# clogic.net
KiCad netlist of a schematic drawn in EAGLE
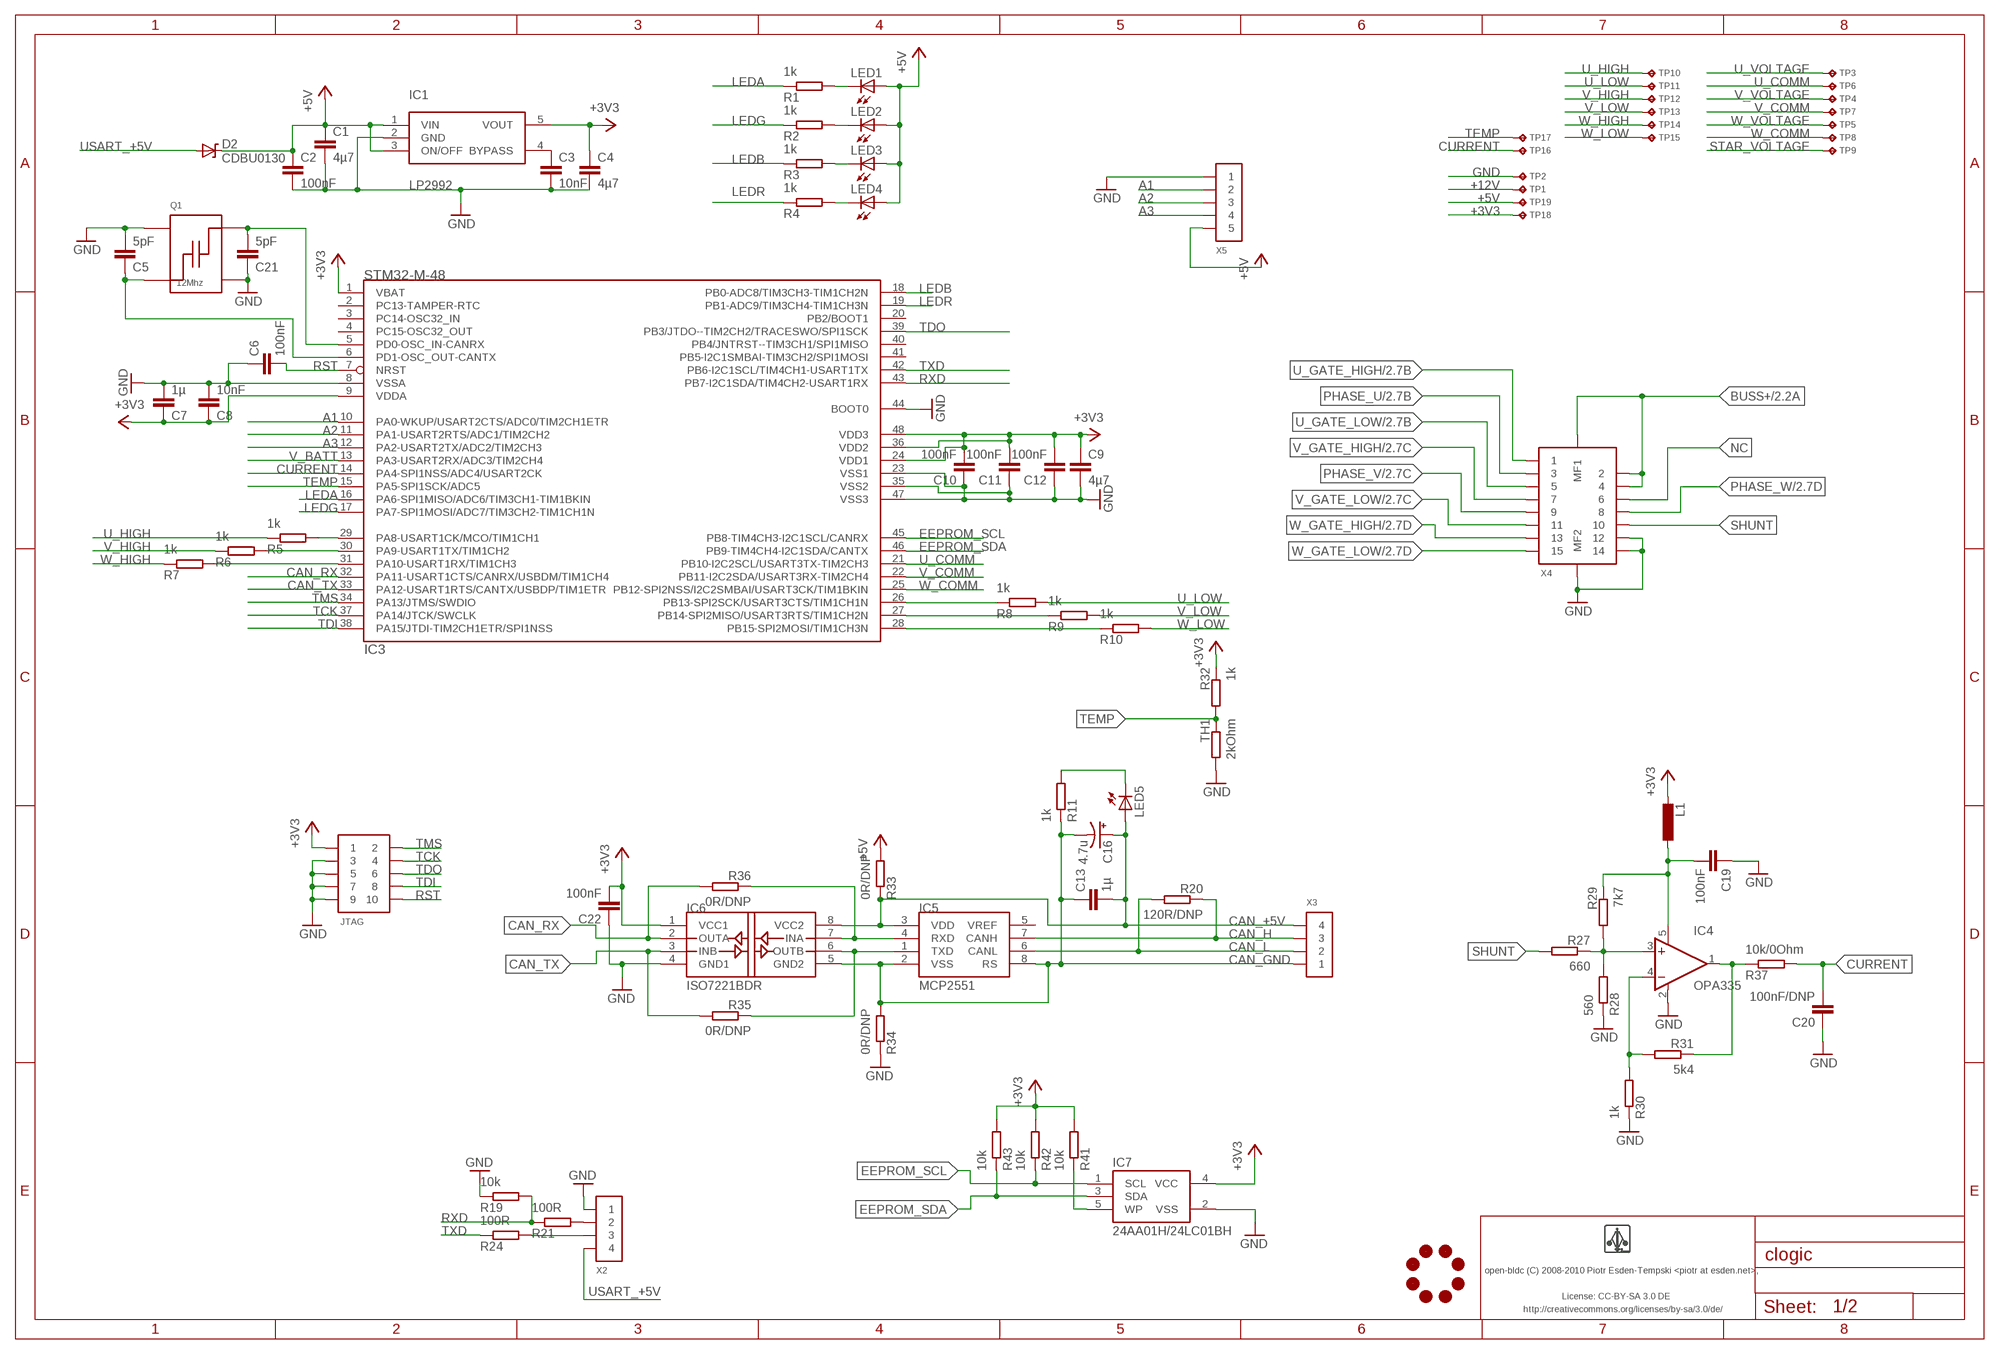
[diagram p0: schematic, sheet 1]
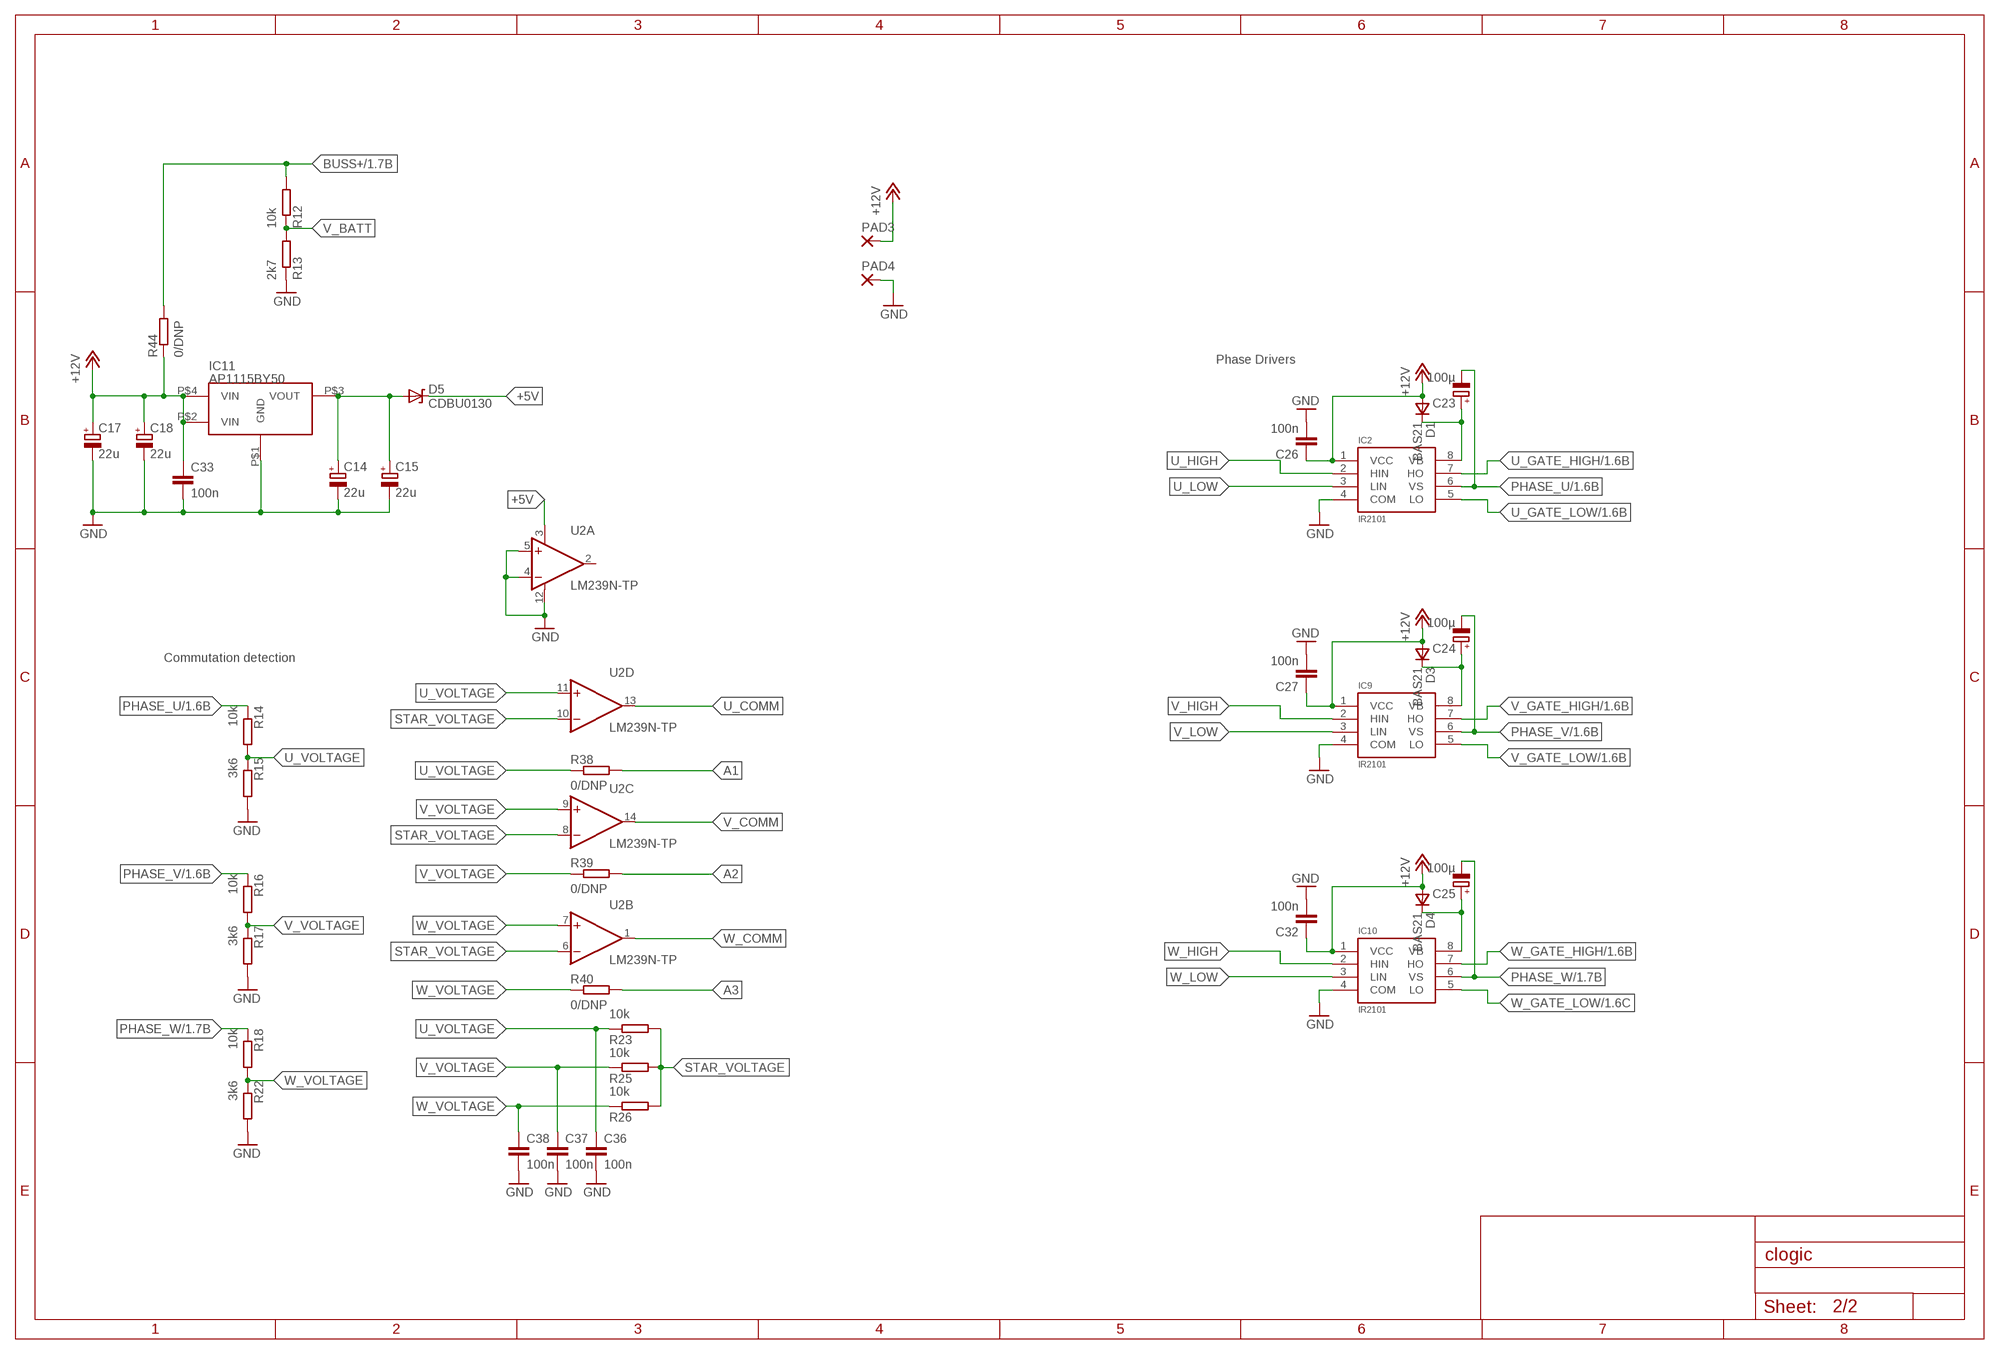
[diagram p1: schematic, sheet 2]

(export (version "E")
  (design (tool "Eeschema 10.0.6"))
  (components
    (comp (ref "C1")
      (value "4µ7")
      (footprint "eagle-import:0603-CAP")
      (libsource (lib "eagle-import") (part "CAPACITOR-0603"))
    )
    (comp (ref "C2")
      (value "100nF")
      (footprint "eagle-import:0603-CAP")
      (libsource (lib "eagle-import") (part "CAPACITOR-0603"))
    )
    (comp (ref "C3")
      (value "10nF")
      (footprint "eagle-import:0603-CAP")
      (libsource (lib "eagle-import") (part "CAPACITOR-0603"))
    )
    (comp (ref "C4")
      (value "4µ7")
      (footprint "eagle-import:0603-CAP")
      (libsource (lib "eagle-import") (part "CAPACITOR-0603"))
    )
    (comp (ref "C5")
      (value "5pF")
      (footprint "eagle-import:0603-CAP")
      (libsource (lib "eagle-import") (part "CAPACITOR-0603"))
    )
    (comp (ref "C6")
      (value "100nF")
      (footprint "eagle-import:0603-CAP")
      (libsource (lib "eagle-import") (part "CAPACITOR-0603"))
    )
    (comp (ref "C7")
      (value "1µ")
      (footprint "eagle-import:0603-CAP")
      (libsource (lib "eagle-import") (part "CAPACITOR-0603"))
    )
    (comp (ref "C8")
      (value "10nF")
      (footprint "eagle-import:0603-CAP")
      (libsource (lib "eagle-import") (part "CAPACITOR-0603"))
    )
    (comp (ref "C9")
      (value "4µ7")
      (footprint "eagle-import:0603-CAP")
      (libsource (lib "eagle-import") (part "CAPACITOR-0603"))
    )
    (comp (ref "C10")
      (value "100nF")
      (footprint "eagle-import:0603-CAP")
      (libsource (lib "eagle-import") (part "CAPACITOR-0603"))
    )
    (comp (ref "C11")
      (value "100nF")
      (footprint "eagle-import:0603-CAP")
      (libsource (lib "eagle-import") (part "CAPACITOR-0603"))
    )
    (comp (ref "C12")
      (value "100nF")
      (footprint "eagle-import:0603-CAP")
      (libsource (lib "eagle-import") (part "CAPACITOR-0603"))
    )
    (comp (ref "C13")
      (value "1µ")
      (footprint "eagle-import:0603-CAP")
      (libsource (lib "eagle-import") (part "CAPACITOR-0603"))
    )
    (comp (ref "C16")
      (value "4.7u")
      (footprint "eagle-import:CAP_0805TANT_F95")
      (libsource (lib "eagle-import") (part "CPOL-US"))
    )
    (comp (ref "C19")
      (value "100nF")
      (footprint "eagle-import:0603-CAP")
      (libsource (lib "eagle-import") (part "CAPACITOR-0603"))
    )
    (comp (ref "C20")
      (value "100nF/DNP")
      (footprint "eagle-import:0603-CAP")
      (libsource (lib "eagle-import") (part "CAPACITOR-0603"))
    )
    (comp (ref "C21")
      (value "5pF")
      (footprint "eagle-import:0603-CAP")
      (libsource (lib "eagle-import") (part "CAPACITOR-0603"))
    )
    (comp (ref "C22")
      (value "100nF")
      (footprint "eagle-import:0603-CAP")
      (libsource (lib "eagle-import") (part "CAPACITOR-0603"))
    )
    (comp (ref "D2")
      (value "CDBU0130")
      (footprint "eagle-import:0603-LED")
      (libsource (lib "eagle-import") (part "DIODE-ZENER-0603"))
    )
    (comp (ref "IC1")
      (value "LP2992")
      (footprint "eagle-import:SOT23-5")
      (libsource (lib "eagle-import") (part "LP2992"))
    )
    (comp (ref "IC3")
      (value "STM32-M-48")
      (footprint "eagle-import:LQFP48")
      (libsource (lib "eagle-import") (part "STM32-M-48"))
    )
    (comp (ref "IC4")
      (value "OPA335")
      (footprint "eagle-import:SOT23-5")
      (libsource (lib "eagle-import") (part "OPA335"))
    )
    (comp (ref "IC5")
      (value "MCP2551")
      (footprint "eagle-import:SO8")
      (libsource (lib "eagle-import") (part "MCP2551"))
    )
    (comp (ref "IC6")
      (value "ISO7221BDR")
      (footprint "eagle-import:SO8")
      (libsource (lib "eagle-import") (part "ISO7221"))
    )
    (comp (ref "IC7")
      (value "24AA01H/24LC01BH")
      (footprint "eagle-import:SOT23-5")
      (libsource (lib "eagle-import") (part "EEPROM-I2C"))
    )
    (comp (ref "JL1")
      (value "JOBY_LOGO-6MIL")
      (footprint "eagle-import:JOBY_LOGO_6MIL")
      (libsource (lib "eagle-import") (part "JOBY_LOGO-6MIL"))
    )
    (comp (ref "JTAG")
      (value "CONN_5-2-FTSH-V")
      (footprint "eagle-import:FTSH-105-DV")
      (libsource (lib "eagle-import") (part "CONN_5-2-FTSH-V"))
    )
    (comp (ref "L1")
      (value "INDUCTOR-0603")
      (footprint "eagle-import:0603-IND")
      (libsource (lib "eagle-import") (part "INDUCTOR-0603"))
    )
    (comp (ref "LED1")
      (value "AMBER")
      (footprint "eagle-import:0603-LED")
      (libsource (lib "eagle-import") (part "LED-0603"))
    )
    (comp (ref "LED2")
      (value "GREEN")
      (footprint "eagle-import:0603-LED")
      (libsource (lib "eagle-import") (part "LED-0603"))
    )
    (comp (ref "LED3")
      (value "BLUE")
      (footprint "eagle-import:0603-LED")
      (libsource (lib "eagle-import") (part "LED-0603"))
    )
    (comp (ref "LED4")
      (value "RED")
      (footprint "eagle-import:0603-LED")
      (libsource (lib "eagle-import") (part "LED-0603"))
    )
    (comp (ref "LED5")
      (value "WHITE")
      (footprint "eagle-import:0603-LED")
      (libsource (lib "eagle-import") (part "LED-0603"))
    )
    (comp (ref "Q1")
      (value "12Mhz")
      (footprint "eagle-import:ABM8")
      (libsource (lib "eagle-import") (part "ABM8"))
    )
    (comp (ref "R1")
      (value "1k")
      (footprint "eagle-import:0603-RES")
      (libsource (lib "eagle-import") (part "RESISTOR-0603"))
    )
    (comp (ref "R2")
      (value "1k")
      (footprint "eagle-import:0603-RES")
      (libsource (lib "eagle-import") (part "RESISTOR-0603"))
    )
    (comp (ref "R3")
      (value "1k")
      (footprint "eagle-import:0603-RES")
      (libsource (lib "eagle-import") (part "RESISTOR-0603"))
    )
    (comp (ref "R4")
      (value "1k")
      (footprint "eagle-import:0603-RES")
      (libsource (lib "eagle-import") (part "RESISTOR-0603"))
    )
    (comp (ref "R5")
      (value "1k")
      (footprint "eagle-import:0603-RES")
      (libsource (lib "eagle-import") (part "RESISTOR-0603"))
    )
    (comp (ref "R6")
      (value "1k")
      (footprint "eagle-import:0603-RES")
      (libsource (lib "eagle-import") (part "RESISTOR-0603"))
    )
    (comp (ref "R7")
      (value "1k")
      (footprint "eagle-import:0603-RES")
      (libsource (lib "eagle-import") (part "RESISTOR-0603"))
    )
    (comp (ref "R8")
      (value "1k")
      (footprint "eagle-import:0603-RES")
      (libsource (lib "eagle-import") (part "RESISTOR-0603"))
    )
    (comp (ref "R9")
      (value "1k")
      (footprint "eagle-import:0603-RES")
      (libsource (lib "eagle-import") (part "RESISTOR-0603"))
    )
    (comp (ref "R10")
      (value "1k")
      (footprint "eagle-import:0603-RES")
      (libsource (lib "eagle-import") (part "RESISTOR-0603"))
    )
    (comp (ref "R11")
      (value "1k")
      (footprint "eagle-import:0603-RES")
      (libsource (lib "eagle-import") (part "RESISTOR-0603"))
    )
    (comp (ref "R19")
      (value "10k")
      (footprint "eagle-import:0603-RES")
      (libsource (lib "eagle-import") (part "RESISTOR-0603"))
    )
    (comp (ref "R20")
      (value "120R/DNP")
      (footprint "eagle-import:0603-RES")
      (libsource (lib "eagle-import") (part "RESISTOR-0603"))
    )
    (comp (ref "R21")
      (value "100R")
      (footprint "eagle-import:0603-RES")
      (libsource (lib "eagle-import") (part "RESISTOR-0603"))
    )
    (comp (ref "R24")
      (value "100R")
      (footprint "eagle-import:0603-RES")
      (libsource (lib "eagle-import") (part "RESISTOR-0603"))
    )
    (comp (ref "R27")
      (value "660")
      (footprint "eagle-import:0603-RES")
      (libsource (lib "eagle-import") (part "RESISTOR-0603"))
    )
    (comp (ref "R28")
      (value "560")
      (footprint "eagle-import:0603-RES")
      (libsource (lib "eagle-import") (part "RESISTOR-0603"))
    )
    (comp (ref "R29")
      (value "7k7")
      (footprint "eagle-import:0603-RES")
      (libsource (lib "eagle-import") (part "RESISTOR-0603"))
    )
    (comp (ref "R30")
      (value "1k")
      (footprint "eagle-import:0603-RES")
      (libsource (lib "eagle-import") (part "RESISTOR-0603"))
    )
    (comp (ref "R31")
      (value "5k4")
      (footprint "eagle-import:0603-RES")
      (libsource (lib "eagle-import") (part "RESISTOR-0603"))
    )
    (comp (ref "R32")
      (value "1k")
      (footprint "eagle-import:0603-RES")
      (libsource (lib "eagle-import") (part "RESISTOR-0603"))
    )
    (comp (ref "R33")
      (value "0R/DNP")
      (footprint "eagle-import:0603-RES")
      (libsource (lib "eagle-import") (part "RESISTOR-0603"))
    )
    (comp (ref "R34")
      (value "0R/DNP")
      (footprint "eagle-import:0603-RES")
      (libsource (lib "eagle-import") (part "RESISTOR-0603"))
    )
    (comp (ref "R35")
      (value "0R/DNP")
      (footprint "eagle-import:0603-RES")
      (libsource (lib "eagle-import") (part "RESISTOR-0603"))
    )
    (comp (ref "R36")
      (value "0R/DNP")
      (footprint "eagle-import:0603-RES")
      (libsource (lib "eagle-import") (part "RESISTOR-0603"))
    )
    (comp (ref "R37")
      (value "10k/0Ohm")
      (footprint "eagle-import:0603-RES")
      (libsource (lib "eagle-import") (part "RESISTOR-0603"))
    )
    (comp (ref "R41")
      (value "10k")
      (footprint "eagle-import:0603-RES")
      (libsource (lib "eagle-import") (part "RESISTOR-0603"))
    )
    (comp (ref "R42")
      (value "10k")
      (footprint "eagle-import:0603-RES")
      (libsource (lib "eagle-import") (part "RESISTOR-0603"))
    )
    (comp (ref "R43")
      (value "10k")
      (footprint "eagle-import:0603-RES")
      (libsource (lib "eagle-import") (part "RESISTOR-0603"))
    )
    (comp (ref "TH1")
      (value "2kOhm")
      (footprint "eagle-import:0603-RES")
      (libsource (lib "eagle-import") (part "RESISTOR-0603"))
    )
    (comp (ref "TP1")
      (value "TP-09RSMD")
      (footprint "eagle-import:TP09R")
      (libsource (lib "eagle-import") (part "TP-09RSMD"))
    )
    (comp (ref "TP2")
      (value "TP-09RSMD")
      (footprint "eagle-import:TP09R")
      (libsource (lib "eagle-import") (part "TP-09RSMD"))
    )
    (comp (ref "TP3")
      (value "TP-09RSMD")
      (footprint "eagle-import:TP09R")
      (libsource (lib "eagle-import") (part "TP-09RSMD"))
    )
    (comp (ref "TP4")
      (value "TP-09RSMD")
      (footprint "eagle-import:TP09R")
      (libsource (lib "eagle-import") (part "TP-09RSMD"))
    )
    (comp (ref "TP5")
      (value "TP-09RSMD")
      (footprint "eagle-import:TP09R")
      (libsource (lib "eagle-import") (part "TP-09RSMD"))
    )
    (comp (ref "TP6")
      (value "TP-09RSMD")
      (footprint "eagle-import:TP09R")
      (libsource (lib "eagle-import") (part "TP-09RSMD"))
    )
    (comp (ref "TP7")
      (value "TP-09RSMD")
      (footprint "eagle-import:TP09R")
      (libsource (lib "eagle-import") (part "TP-09RSMD"))
    )
    (comp (ref "TP8")
      (value "TP-09RSMD")
      (footprint "eagle-import:TP09R")
      (libsource (lib "eagle-import") (part "TP-09RSMD"))
    )
    (comp (ref "TP9")
      (value "TP-09RSMD")
      (footprint "eagle-import:TP09R")
      (libsource (lib "eagle-import") (part "TP-09RSMD"))
    )
    (comp (ref "TP10")
      (value "TP-09RSMD")
      (footprint "eagle-import:TP09R")
      (libsource (lib "eagle-import") (part "TP-09RSMD"))
    )
    (comp (ref "TP11")
      (value "TP-09RSMD")
      (footprint "eagle-import:TP09R")
      (libsource (lib "eagle-import") (part "TP-09RSMD"))
    )
    (comp (ref "TP12")
      (value "TP-09RSMD")
      (footprint "eagle-import:TP09R")
      (libsource (lib "eagle-import") (part "TP-09RSMD"))
    )
    (comp (ref "TP13")
      (value "TP-09RSMD")
      (footprint "eagle-import:TP09R")
      (libsource (lib "eagle-import") (part "TP-09RSMD"))
    )
    (comp (ref "TP14")
      (value "TP-09RSMD")
      (footprint "eagle-import:TP09R")
      (libsource (lib "eagle-import") (part "TP-09RSMD"))
    )
    (comp (ref "TP15")
      (value "TP-09RSMD")
      (footprint "eagle-import:TP09R")
      (libsource (lib "eagle-import") (part "TP-09RSMD"))
    )
    (comp (ref "TP16")
      (value "TP-09RSMD")
      (footprint "eagle-import:TP09R")
      (libsource (lib "eagle-import") (part "TP-09RSMD"))
    )
    (comp (ref "TP17")
      (value "TP-09RSMD")
      (footprint "eagle-import:TP09R")
      (libsource (lib "eagle-import") (part "TP-09RSMD"))
    )
    (comp (ref "TP18")
      (value "TP-09RSMD")
      (footprint "eagle-import:TP09R")
      (libsource (lib "eagle-import") (part "TP-09RSMD"))
    )
    (comp (ref "TP19")
      (value "TP-09RSMD")
      (footprint "eagle-import:TP09R")
      (libsource (lib "eagle-import") (part "TP-09RSMD"))
    )
    (comp (ref "U$1")
      (value "LOGO")
      (footprint "eagle-import:LOGO")
      (libsource (lib "eagle-import") (part "LOGO-NORM"))
    )
    (comp (ref "X2")
      (value "CONN_4-1-53261")
      (footprint "eagle-import:PB-53261-04")
      (libsource (lib "eagle-import") (part "CONN_4-1-53261"))
    )
    (comp (ref "X3")
      (value "CONN_4-1-53261")
      (footprint "eagle-import:PB-53261-04")
      (libsource (lib "eagle-import") (part "CONN_4-1-53261"))
    )
    (comp (ref "X4")
      (value "CONN_15-2-2MT-DF9")
      (footprint "eagle-import:DF9-15")
      (libsource (lib "eagle-import") (part "CONN_15-2-2MT-DF9"))
    )
    (comp (ref "X5")
      (value "CONN_5-1-53261")
      (footprint "eagle-import:PB-53261-05")
      (libsource (lib "eagle-import") (part "CONN_5-1-53261"))
    )
    (comp (ref "C14")
      (value "22u")
      (footprint "eagle-import:0805-POL-CAP")
      (libsource (lib "eagle-import") (part "CAPACITOR-POL-0805"))
    )
    (comp (ref "C15")
      (value "22u")
      (footprint "eagle-import:0805-POL-CAP")
      (libsource (lib "eagle-import") (part "CAPACITOR-POL-0805"))
    )
    (comp (ref "C17")
      (value "22u")
      (footprint "eagle-import:0805-POL-CAP")
      (libsource (lib "eagle-import") (part "CAPACITOR-POL-0805"))
    )
    (comp (ref "C18")
      (value "22u")
      (footprint "eagle-import:0805-POL-CAP")
      (libsource (lib "eagle-import") (part "CAPACITOR-POL-0805"))
    )
    (comp (ref "C23")
      (value "100µ")
      (footprint "eagle-import:0805-POL-CAP")
      (libsource (lib "eagle-import") (part "CAPACITOR-POL-0805"))
    )
    (comp (ref "C24")
      (value "100µ")
      (footprint "eagle-import:0805-POL-CAP")
      (libsource (lib "eagle-import") (part "CAPACITOR-POL-0805"))
    )
    (comp (ref "C25")
      (value "100µ")
      (footprint "eagle-import:0805-POL-CAP")
      (libsource (lib "eagle-import") (part "CAPACITOR-POL-0805"))
    )
    (comp (ref "C26")
      (value "100n")
      (footprint "eagle-import:0603-CAP")
      (libsource (lib "eagle-import") (part "CAPACITOR-0603"))
    )
    (comp (ref "C27")
      (value "100n")
      (footprint "eagle-import:0603-CAP")
      (libsource (lib "eagle-import") (part "CAPACITOR-0603"))
    )
    (comp (ref "C32")
      (value "100n")
      (footprint "eagle-import:0603-CAP")
      (libsource (lib "eagle-import") (part "CAPACITOR-0603"))
    )
    (comp (ref "C33")
      (value "100n")
      (footprint "eagle-import:0603-CAP")
      (libsource (lib "eagle-import") (part "CAPACITOR-0603"))
    )
    (comp (ref "C36")
      (value "100n")
      (footprint "eagle-import:0603-CAP")
      (libsource (lib "eagle-import") (part "CAPACITOR-0603"))
    )
    (comp (ref "C37")
      (value "100n")
      (footprint "eagle-import:0603-CAP")
      (libsource (lib "eagle-import") (part "CAPACITOR-0603"))
    )
    (comp (ref "C38")
      (value "100n")
      (footprint "eagle-import:0603-CAP")
      (libsource (lib "eagle-import") (part "CAPACITOR-0603"))
    )
    (comp (ref "D1")
      (value "BAS21")
      (footprint "eagle-import:SOT-23")
      (libsource (lib "eagle-import") (part "VAR2SOT23"))
    )
    (comp (ref "D3")
      (value "BAS21")
      (footprint "eagle-import:SOT-23")
      (libsource (lib "eagle-import") (part "VAR2SOT23"))
    )
    (comp (ref "D4")
      (value "BAS21")
      (footprint "eagle-import:SOT-23")
      (libsource (lib "eagle-import") (part "VAR2SOT23"))
    )
    (comp (ref "D5")
      (value "CDBU0130")
      (footprint "eagle-import:0603-LED")
      (libsource (lib "eagle-import") (part "DIODE-ZENER-0603"))
    )
    (comp (ref "IC2")
      (value "IR2101")
      (footprint "eagle-import:SO-8")
      (libsource (lib "eagle-import") (part "IR2101"))
    )
    (comp (ref "IC9")
      (value "IR2101")
      (footprint "eagle-import:SO-8")
      (libsource (lib "eagle-import") (part "IR2101"))
    )
    (comp (ref "IC10")
      (value "IR2101")
      (footprint "eagle-import:SO-8")
      (libsource (lib "eagle-import") (part "IR2101"))
    )
    (comp (ref "IC11")
      (value "AP1115BY50")
      (footprint "eagle-import:SOT89")
      (libsource (lib "eagle-import") (part "AP1115BY50"))
    )
    (comp (ref "PAD3")
      (value "SMD5")
      (footprint "eagle-import:SMD2,54-5,08")
      (libsource (lib "eagle-import") (part "SMD5"))
    )
    (comp (ref "PAD4")
      (value "SMD5")
      (footprint "eagle-import:SMD2,54-5,08")
      (libsource (lib "eagle-import") (part "SMD5"))
    )
    (comp (ref "R12")
      (value "10k")
      (footprint "eagle-import:0603-RES")
      (libsource (lib "eagle-import") (part "RESISTOR-0603"))
    )
    (comp (ref "R13")
      (value "2k7")
      (footprint "eagle-import:0603-RES")
      (libsource (lib "eagle-import") (part "RESISTOR-0603"))
    )
    (comp (ref "R14")
      (value "10k")
      (footprint "eagle-import:0603-RES")
      (libsource (lib "eagle-import") (part "RESISTOR-0603"))
    )
    (comp (ref "R15")
      (value "3k6")
      (footprint "eagle-import:0603-RES")
      (libsource (lib "eagle-import") (part "RESISTOR-0603"))
    )
    (comp (ref "R16")
      (value "10k")
      (footprint "eagle-import:0603-RES")
      (libsource (lib "eagle-import") (part "RESISTOR-0603"))
    )
    (comp (ref "R17")
      (value "3k6")
      (footprint "eagle-import:0603-RES")
      (libsource (lib "eagle-import") (part "RESISTOR-0603"))
    )
    (comp (ref "R18")
      (value "10k")
      (footprint "eagle-import:0603-RES")
      (libsource (lib "eagle-import") (part "RESISTOR-0603"))
    )
    (comp (ref "R22")
      (value "3k6")
      (footprint "eagle-import:0603-RES")
      (libsource (lib "eagle-import") (part "RESISTOR-0603"))
    )
    (comp (ref "R23")
      (value "10k")
      (footprint "eagle-import:0603-RES")
      (libsource (lib "eagle-import") (part "RESISTOR-0603"))
    )
    (comp (ref "R25")
      (value "10k")
      (footprint "eagle-import:0603-RES")
      (libsource (lib "eagle-import") (part "RESISTOR-0603"))
    )
    (comp (ref "R26")
      (value "10k")
      (footprint "eagle-import:0603-RES")
      (libsource (lib "eagle-import") (part "RESISTOR-0603"))
    )
    (comp (ref "R38")
      (value "0/DNP")
      (footprint "eagle-import:0603-RES")
      (libsource (lib "eagle-import") (part "RESISTOR-0603"))
    )
    (comp (ref "R39")
      (value "0/DNP")
      (footprint "eagle-import:0603-RES")
      (libsource (lib "eagle-import") (part "RESISTOR-0603"))
    )
    (comp (ref "R40")
      (value "0/DNP")
      (footprint "eagle-import:0603-RES")
      (libsource (lib "eagle-import") (part "RESISTOR-0603"))
    )
    (comp (ref "R44")
      (value "0/DNP")
      (footprint "eagle-import:0603-RES")
      (libsource (lib "eagle-import") (part "RESISTOR-0603"))
    )
    (comp (ref "U2")
      (value "LM239N-TP")
      (footprint "eagle-import:TSSOP_14")
      (libsource (lib "eagle-import") (part "LM239N-TP"))
    )
  )
  (nets
    (net (code "1") (name "+3V3") (class "Default")
      (node (ref "C10") (pin "P$2") (pinfunction "2_P$2") (pintype "passive"))
      (node (ref "C11") (pin "P$2") (pinfunction "2_P$2") (pintype "passive"))
      (node (ref "C12") (pin "P$2") (pinfunction "2_P$2") (pintype "passive"))
      (node (ref "C22") (pin "P$2") (pinfunction "2_P$2") (pintype "passive"))
      (node (ref "C4") (pin "P$1") (pinfunction "1_P$1") (pintype "passive"))
      (node (ref "C7") (pin "P$1") (pinfunction "1_P$1") (pintype "passive"))
      (node (ref "C8") (pin "P$1") (pinfunction "1_P$1") (pintype "passive"))
      (node (ref "C9") (pin "P$1") (pinfunction "1_P$1") (pintype "passive"))
      (node (ref "IC1") (pin "5") (pinfunction "VOUT_5") (pintype "bidirectional"))
      (node (ref "IC3") (pin "1") (pinfunction "VBAT_1") (pintype "power_in"))
      (node (ref "IC3") (pin "24") (pinfunction "VDD1_24") (pintype "power_in"))
      (node (ref "IC3") (pin "36") (pinfunction "VDD2_36") (pintype "power_in"))
      (node (ref "IC3") (pin "48") (pinfunction "VDD3_48") (pintype "power_in"))
      (node (ref "IC3") (pin "9") (pinfunction "VDDA_9") (pintype "power_in"))
      (node (ref "IC6") (pin "1") (pinfunction "VCC1_1") (pintype "bidirectional"))
      (node (ref "IC7") (pin "4") (pinfunction "VCC_4") (pintype "bidirectional"))
      (node (ref "JTAG") (pin "1") (pinfunction "1_1") (pintype "bidirectional"))
      (node (ref "L1") (pin "P$2") (pinfunction "2_P$2") (pintype "passive"))
      (node (ref "R32") (pin "P$1") (pinfunction "1_P$1") (pintype "passive"))
      (node (ref "R41") (pin "P$2") (pinfunction "2_P$2") (pintype "passive"))
      (node (ref "R42") (pin "P$2") (pinfunction "2_P$2") (pintype "passive"))
      (node (ref "R43") (pin "P$2") (pinfunction "2_P$2") (pintype "passive"))
      (node (ref "TP18") (pin "P$1") (pinfunction "1_P$1") (pintype "bidirectional"))
    )
    (net (code "2") (name "+5V") (class "Default")
      (node (ref "C1") (pin "P$1") (pinfunction "1_P$1") (pintype "passive"))
      (node (ref "C2") (pin "P$1") (pinfunction "1_P$1") (pintype "passive"))
      (node (ref "D2") (pin "C") (pinfunction "C_C") (pintype "passive"))
      (node (ref "D5") (pin "C") (pinfunction "C_C") (pintype "passive"))
      (node (ref "IC1") (pin "1") (pinfunction "VIN_1") (pintype "bidirectional"))
      (node (ref "IC1") (pin "3") (pinfunction "ON/OFF_3") (pintype "bidirectional"))
      (node (ref "LED1") (pin "A") (pinfunction "A_A") (pintype "passive"))
      (node (ref "LED2") (pin "A") (pinfunction "A_A") (pintype "passive"))
      (node (ref "LED3") (pin "A") (pinfunction "A_A") (pintype "passive"))
      (node (ref "LED4") (pin "A") (pinfunction "A_A") (pintype "passive"))
      (node (ref "R33") (pin "P$2") (pinfunction "2_P$2") (pintype "passive"))
      (node (ref "TP19") (pin "P$1") (pinfunction "1_P$1") (pintype "bidirectional"))
      (node (ref "U2") (pin "3") (pinfunction "V+_3") (pintype "power_in"))
      (node (ref "X5") (pin "5") (pinfunction "5_5") (pintype "bidirectional"))
    )
    (net (code "3") (name "+12V") (class "Default")
      (node (ref "C17") (pin "+") (pinfunction "+_+") (pintype "passive"))
      (node (ref "C18") (pin "+") (pinfunction "+_+") (pintype "passive"))
      (node (ref "C26") (pin "P$1") (pinfunction "1_P$1") (pintype "passive"))
      (node (ref "C27") (pin "P$1") (pinfunction "1_P$1") (pintype "passive"))
      (node (ref "C32") (pin "P$1") (pinfunction "1_P$1") (pintype "passive"))
      (node (ref "C33") (pin "P$1") (pinfunction "1_P$1") (pintype "passive"))
      (node (ref "D1") (pin "3") (pinfunction "A_3") (pintype "passive"))
      (node (ref "D3") (pin "3") (pinfunction "A_3") (pintype "passive"))
      (node (ref "D4") (pin "3") (pinfunction "A_3") (pintype "passive"))
      (node (ref "IC10") (pin "1") (pinfunction "VCC_1") (pintype "bidirectional"))
      (node (ref "IC11") (pin "P$2") (pinfunction "VIN_P$2") (pintype "power_in"))
      (node (ref "IC11") (pin "P$4") (pinfunction "VIN_P$4") (pintype "input"))
      (node (ref "IC2") (pin "1") (pinfunction "VCC_1") (pintype "bidirectional"))
      (node (ref "IC9") (pin "1") (pinfunction "VCC_1") (pintype "bidirectional"))
      (node (ref "PAD3") (pin "1") (pinfunction "P_1") (pintype "passive"))
      (node (ref "R44") (pin "P$1") (pinfunction "1_P$1") (pintype "passive"))
      (node (ref "TP1") (pin "P$1") (pinfunction "1_P$1") (pintype "bidirectional"))
    )
    (net (code "4") (name "A1") (class "Default")
      (node (ref "IC3") (pin "10") (pinfunction "PA0-WKUP/USART2CTS/ADC0/TIM2CH1ETR_10") (pintype "bidirectional"))
      (node (ref "R38") (pin "P$2") (pinfunction "2_P$2") (pintype "passive"))
      (node (ref "X5") (pin "2") (pinfunction "2_2") (pintype "bidirectional"))
    )
    (net (code "5") (name "A2") (class "Default")
      (node (ref "IC3") (pin "11") (pinfunction "PA1-USART2RTS/ADC1/TIM2CH2_11") (pintype "bidirectional"))
      (node (ref "R39") (pin "P$2") (pinfunction "2_P$2") (pintype "passive"))
      (node (ref "X5") (pin "3") (pinfunction "3_3") (pintype "bidirectional"))
    )
    (net (code "6") (name "A3") (class "Default")
      (node (ref "IC3") (pin "12") (pinfunction "PA2-USART2TX/ADC2/TIM2CH3_12") (pintype "bidirectional"))
      (node (ref "R40") (pin "P$2") (pinfunction "2_P$2") (pintype "passive"))
      (node (ref "X5") (pin "4") (pinfunction "4_4") (pintype "bidirectional"))
    )
    (net (code "7") (name "BUSS+") (class "Default")
      (node (ref "R12") (pin "P$2") (pinfunction "2_P$2") (pintype "passive"))
      (node (ref "R44") (pin "P$2") (pinfunction "2_P$2") (pintype "passive"))
      (node (ref "X4") (pin "2") (pinfunction "2_2") (pintype "bidirectional"))
      (node (ref "X4") (pin "4") (pinfunction "4_4") (pintype "bidirectional"))
      (node (ref "X4") (pin "MF1") (pinfunction "MF1_MF1") (pintype "bidirectional"))
    )
    (net (code "8") (name "CAN_+5V") (class "Default")
      (node (ref "C13") (pin "P$2") (pinfunction "2_P$2") (pintype "passive"))
      (node (ref "C16") (pin "P$1") (pinfunction "+_P$1") (pintype "passive"))
      (node (ref "IC5") (pin "3") (pinfunction "VDD_3") (pintype "bidirectional"))
      (node (ref "IC6") (pin "8") (pinfunction "VCC2_8") (pintype "bidirectional"))
      (node (ref "LED5") (pin "A") (pinfunction "A_A") (pintype "passive"))
      (node (ref "R33") (pin "P$1") (pinfunction "1_P$1") (pintype "passive"))
      (node (ref "X3") (pin "4") (pinfunction "4_4") (pintype "bidirectional"))
    )
    (net (code "9") (name "CAN_GND") (class "Default")
      (node (ref "C13") (pin "P$1") (pinfunction "1_P$1") (pintype "passive"))
      (node (ref "C16") (pin "P$2") (pinfunction "-_P$2") (pintype "passive"))
      (node (ref "IC5") (pin "2") (pinfunction "VSS_2") (pintype "bidirectional"))
      (node (ref "IC5") (pin "8") (pinfunction "RS_8") (pintype "bidirectional"))
      (node (ref "IC6") (pin "5") (pinfunction "GND2_5") (pintype "bidirectional"))
      (node (ref "R11") (pin "P$1") (pinfunction "1_P$1") (pintype "passive"))
      (node (ref "R34") (pin "P$2") (pinfunction "2_P$2") (pintype "passive"))
      (node (ref "X3") (pin "1") (pinfunction "1_1") (pintype "bidirectional"))
    )
    (net (code "10") (name "CAN_H") (class "Default")
      (node (ref "IC5") (pin "7") (pinfunction "CANH_7") (pintype "bidirectional"))
      (node (ref "R20") (pin "P$1") (pinfunction "1_P$1") (pintype "passive"))
      (node (ref "X3") (pin "3") (pinfunction "3_3") (pintype "bidirectional"))
    )
    (net (code "11") (name "CAN_L") (class "Default")
      (node (ref "IC5") (pin "6") (pinfunction "CANL_6") (pintype "bidirectional"))
      (node (ref "R20") (pin "P$2") (pinfunction "2_P$2") (pintype "passive"))
      (node (ref "X3") (pin "2") (pinfunction "2_2") (pintype "bidirectional"))
    )
    (net (code "12") (name "CAN_RX") (class "Default")
      (node (ref "IC3") (pin "32") (pinfunction "PA11-USART1CTS/CANRX/USBDM/TIM1CH4_32") (pintype "bidirectional"))
      (node (ref "IC6") (pin "2") (pinfunction "OUTA_2") (pintype "bidirectional"))
      (node (ref "R36") (pin "P$2") (pinfunction "2_P$2") (pintype "passive"))
    )
    (net (code "13") (name "CAN_TX") (class "Default")
      (node (ref "IC3") (pin "33") (pinfunction "PA12-USART1RTS/CANTX/USBDP/TIM1ETR_33") (pintype "bidirectional"))
      (node (ref "IC6") (pin "3") (pinfunction "INB_3") (pintype "bidirectional"))
      (node (ref "R35") (pin "P$2") (pinfunction "2_P$2") (pintype "passive"))
    )
    (net (code "14") (name "CURRENT") (class "Default")
      (node (ref "C20") (pin "P$2") (pinfunction "2_P$2") (pintype "passive"))
      (node (ref "IC3") (pin "14") (pinfunction "PA4-SPI1NSS/ADC4/USART2CK_14") (pintype "bidirectional"))
      (node (ref "R37") (pin "P$2") (pinfunction "2_P$2") (pintype "passive"))
      (node (ref "TP16") (pin "P$1") (pinfunction "1_P$1") (pintype "bidirectional"))
    )
    (net (code "15") (name "EEPROM_SCL") (class "Default")
      (node (ref "IC3") (pin "45") (pinfunction "PB8-TIM4CH3-I2C1SCL/CANRX_45") (pintype "bidirectional"))
      (node (ref "IC7") (pin "1") (pinfunction "SCL_1") (pintype "bidirectional"))
      (node (ref "R42") (pin "P$1") (pinfunction "1_P$1") (pintype "passive"))
    )
    (net (code "16") (name "EEPROM_SDA") (class "Default")
      (node (ref "IC3") (pin "46") (pinfunction "PB9-TIM4CH4-I2C1SDA/CANTX_46") (pintype "bidirectional"))
      (node (ref "IC7") (pin "3") (pinfunction "SDA_3") (pintype "bidirectional"))
      (node (ref "R43") (pin "P$1") (pinfunction "1_P$1") (pintype "passive"))
    )
    (net (code "17") (name "GND") (class "Default")
      (node (ref "C1") (pin "P$2") (pinfunction "2_P$2") (pintype "passive"))
      (node (ref "C10") (pin "P$1") (pinfunction "1_P$1") (pintype "passive"))
      (node (ref "C11") (pin "P$1") (pinfunction "1_P$1") (pintype "passive"))
      (node (ref "C12") (pin "P$1") (pinfunction "1_P$1") (pintype "passive"))
      (node (ref "C14") (pin "-") (pinfunction "-_-") (pintype "passive"))
      (node (ref "C15") (pin "-") (pinfunction "-_-") (pintype "passive"))
      (node (ref "C17") (pin "-") (pinfunction "-_-") (pintype "passive"))
      (node (ref "C18") (pin "-") (pinfunction "-_-") (pintype "passive"))
      (node (ref "C19") (pin "P$1") (pinfunction "1_P$1") (pintype "passive"))
      (node (ref "C2") (pin "P$2") (pinfunction "2_P$2") (pintype "passive"))
      (node (ref "C20") (pin "P$1") (pinfunction "1_P$1") (pintype "passive"))
      (node (ref "C21") (pin "P$1") (pinfunction "1_P$1") (pintype "passive"))
      (node (ref "C22") (pin "P$1") (pinfunction "1_P$1") (pintype "passive"))
      (node (ref "C26") (pin "P$2") (pinfunction "2_P$2") (pintype "passive"))
      (node (ref "C27") (pin "P$2") (pinfunction "2_P$2") (pintype "passive"))
      (node (ref "C3") (pin "P$2") (pinfunction "2_P$2") (pintype "passive"))
      (node (ref "C32") (pin "P$2") (pinfunction "2_P$2") (pintype "passive"))
      (node (ref "C33") (pin "P$2") (pinfunction "2_P$2") (pintype "passive"))
      (node (ref "C36") (pin "P$2") (pinfunction "2_P$2") (pintype "passive"))
      (node (ref "C37") (pin "P$2") (pinfunction "2_P$2") (pintype "passive"))
      (node (ref "C38") (pin "P$2") (pinfunction "2_P$2") (pintype "passive"))
      (node (ref "C4") (pin "P$2") (pinfunction "2_P$2") (pintype "passive"))
      (node (ref "C5") (pin "P$2") (pinfunction "2_P$2") (pintype "passive"))
      (node (ref "C6") (pin "P$1") (pinfunction "1_P$1") (pintype "passive"))
      (node (ref "C7") (pin "P$2") (pinfunction "2_P$2") (pintype "passive"))
      (node (ref "C8") (pin "P$2") (pinfunction "2_P$2") (pintype "passive"))
      (node (ref "C9") (pin "P$2") (pinfunction "2_P$2") (pintype "passive"))
      (node (ref "IC1") (pin "2") (pinfunction "GND_2") (pintype "bidirectional"))
      (node (ref "IC10") (pin "4") (pinfunction "COM_4") (pintype "bidirectional"))
      (node (ref "IC11") (pin "P$1") (pinfunction "GND_P$1") (pintype "power_in"))
      (node (ref "IC2") (pin "4") (pinfunction "COM_4") (pintype "bidirectional"))
      (node (ref "IC3") (pin "23") (pinfunction "VSS1_23") (pintype "power_in"))
      (node (ref "IC3") (pin "35") (pinfunction "VSS2_35") (pintype "power_in"))
      (node (ref "IC3") (pin "44") (pinfunction "BOOT0_44") (pintype "input"))
      (node (ref "IC3") (pin "47") (pinfunction "VSS3_47") (pintype "power_in"))
      (node (ref "IC3") (pin "8") (pinfunction "VSSA_8") (pintype "power_in"))
      (node (ref "IC4") (pin "2") (pinfunction "V-_2") (pintype "power_in"))
      (node (ref "IC6") (pin "4") (pinfunction "GND1_4") (pintype "bidirectional"))
      (node (ref "IC7") (pin "2") (pinfunction "VSS_2") (pintype "bidirectional"))
      (node (ref "IC9") (pin "4") (pinfunction "COM_4") (pintype "bidirectional"))
      (node (ref "JTAG") (pin "3") (pinfunction "3_3") (pintype "bidirectional"))
      (node (ref "JTAG") (pin "5") (pinfunction "5_5") (pintype "bidirectional"))
      (node (ref "JTAG") (pin "7") (pinfunction "7_7") (pintype "bidirectional"))
      (node (ref "JTAG") (pin "9") (pinfunction "9_9") (pintype "bidirectional"))
      (node (ref "PAD4") (pin "1") (pinfunction "P_1") (pintype "passive"))
      (node (ref "Q1") (pin "P$2") (pinfunction "P$2_P$2") (pintype "bidirectional"))
      (node (ref "Q1") (pin "P$4") (pinfunction "P$4_P$4") (pintype "bidirectional"))
      (node (ref "R13") (pin "P$1") (pinfunction "1_P$1") (pintype "passive"))
      (node (ref "R15") (pin "P$2") (pinfunction "2_P$2") (pintype "passive"))
      (node (ref "R17") (pin "P$2") (pinfunction "2_P$2") (pintype "passive"))
      (node (ref "R19") (pin "P$1") (pinfunction "1_P$1") (pintype "passive"))
      (node (ref "R22") (pin "P$2") (pinfunction "2_P$2") (pintype "passive"))
      (node (ref "R28") (pin "P$1") (pinfunction "1_P$1") (pintype "passive"))
      (node (ref "R30") (pin "P$1") (pinfunction "1_P$1") (pintype "passive"))
      (node (ref "R34") (pin "P$1") (pinfunction "1_P$1") (pintype "passive"))
      (node (ref "TH1") (pin "P$2") (pinfunction "2_P$2") (pintype "passive"))
      (node (ref "TP2") (pin "P$1") (pinfunction "1_P$1") (pintype "bidirectional"))
      (node (ref "U2") (pin "12") (pinfunction "V-_12") (pintype "power_in"))
      (node (ref "U2") (pin "4") (pinfunction "-IN_4") (pintype "input"))
      (node (ref "U2") (pin "5") (pinfunction "+IN_5") (pintype "input"))
      (node (ref "X2") (pin "1") (pinfunction "1_1") (pintype "bidirectional"))
      (node (ref "X4") (pin "12") (pinfunction "12_12") (pintype "bidirectional"))
      (node (ref "X4") (pin "14") (pinfunction "14_14") (pintype "bidirectional"))
      (node (ref "X4") (pin "MF2") (pinfunction "MF2_MF2") (pintype "bidirectional"))
      (node (ref "X5") (pin "1") (pinfunction "1_1") (pintype "bidirectional"))
    )
    (net (code "18") (name "LEDA") (class "Default")
      (node (ref "IC3") (pin "16") (pinfunction "PA6-SPI1MISO/ADC6/TIM3CH1-TIM1BKIN_16") (pintype "bidirectional"))
      (node (ref "R1") (pin "P$1") (pinfunction "1_P$1") (pintype "passive"))
    )
    (net (code "19") (name "LEDB") (class "Default")
      (node (ref "IC3") (pin "18") (pinfunction "PB0-ADC8/TIM3CH3-TIM1CH2N_18") (pintype "bidirectional"))
      (node (ref "R3") (pin "P$1") (pinfunction "1_P$1") (pintype "passive"))
    )
    (net (code "20") (name "LEDG") (class "Default")
      (node (ref "IC3") (pin "17") (pinfunction "PA7-SPI1MOSI/ADC7/TIM3CH2-TIM1CH1N_17") (pintype "bidirectional"))
      (node (ref "R2") (pin "P$1") (pinfunction "1_P$1") (pintype "passive"))
    )
    (net (code "21") (name "LEDR") (class "Default")
      (node (ref "IC3") (pin "19") (pinfunction "PB1-ADC9/TIM3CH4-TIM1CH3N_19") (pintype "bidirectional"))
      (node (ref "R4") (pin "P$1") (pinfunction "1_P$1") (pintype "passive"))
    )
    (net (code "22") (name "NC") (class "Default")
      (node (ref "X4") (pin "6") (pinfunction "6_6") (pintype "bidirectional"))
    )
    (net (code "23") (name "Net-(C3-1)") (class "Default")
      (node (ref "C3") (pin "P$1") (pinfunction "1_P$1") (pintype "passive"))
      (node (ref "IC1") (pin "4") (pinfunction "BYPASS_4") (pintype "bidirectional"))
    )
    (net (code "24") (name "Net-(C5-1)") (class "Default")
      (node (ref "C5") (pin "P$1") (pinfunction "1_P$1") (pintype "passive"))
      (node (ref "IC3") (pin "6") (pinfunction "PD1-OSC_OUT-CANTX_6") (pintype "output"))
      (node (ref "Q1") (pin "P$1") (pinfunction "P$1_P$1") (pintype "bidirectional"))
    )
    (net (code "25") (name "Net-(C19-2)") (class "Default")
      (node (ref "C19") (pin "P$2") (pinfunction "2_P$2") (pintype "passive"))
      (node (ref "IC4") (pin "5") (pinfunction "V+_5") (pintype "power_in"))
      (node (ref "L1") (pin "P$1") (pinfunction "1_P$1") (pintype "passive"))
      (node (ref "R29") (pin "P$1") (pinfunction "1_P$1") (pintype "passive"))
    )
    (net (code "26") (name "Net-(C21-2)") (class "Default")
      (node (ref "C21") (pin "P$2") (pinfunction "2_P$2") (pintype "passive"))
      (node (ref "IC3") (pin "5") (pinfunction "PD0-OSC_IN-CANRX_5") (pintype "input"))
      (node (ref "Q1") (pin "P$3") (pinfunction "P$3_P$3") (pintype "bidirectional"))
    )
    (net (code "27") (name "Net-(D1-C)") (class "Default")
      (node (ref "C23") (pin "+") (pinfunction "+_+") (pintype "passive"))
      (node (ref "D1") (pin "1") (pinfunction "C_1") (pintype "passive"))
      (node (ref "IC2") (pin "8") (pinfunction "VB_8") (pintype "bidirectional"))
    )
    (net (code "28") (name "Net-(D3-C)") (class "Default")
      (node (ref "C24") (pin "+") (pinfunction "+_+") (pintype "passive"))
      (node (ref "D3") (pin "1") (pinfunction "C_1") (pintype "passive"))
      (node (ref "IC9") (pin "8") (pinfunction "VB_8") (pintype "bidirectional"))
    )
    (net (code "29") (name "Net-(D4-C)") (class "Default")
      (node (ref "C25") (pin "+") (pinfunction "+_+") (pintype "passive"))
      (node (ref "D4") (pin "1") (pinfunction "C_1") (pintype "passive"))
      (node (ref "IC10") (pin "8") (pinfunction "VB_8") (pintype "bidirectional"))
    )
    (net (code "30") (name "Net-(IC3-PA8-USART1CK{slash}MCO{slash}TIM1CH1)") (class "Default")
      (node (ref "IC3") (pin "29") (pinfunction "PA8-USART1CK/MCO/TIM1CH1_29") (pintype "bidirectional"))
      (node (ref "R5") (pin "P$2") (pinfunction "2_P$2") (pintype "passive"))
    )
    (net (code "31") (name "Net-(IC3-PA9-USART1TX{slash}TIM1CH2)") (class "Default")
      (node (ref "IC3") (pin "30") (pinfunction "PA9-USART1TX/TIM1CH2_30") (pintype "bidirectional"))
      (node (ref "R6") (pin "P$2") (pinfunction "2_P$2") (pintype "passive"))
    )
    (net (code "32") (name "Net-(IC3-PA10-USART1RX{slash}TIM1CH3)") (class "Default")
      (node (ref "IC3") (pin "31") (pinfunction "PA10-USART1RX/TIM1CH3_31") (pintype "bidirectional"))
      (node (ref "R7") (pin "P$2") (pinfunction "2_P$2") (pintype "passive"))
    )
    (net (code "33") (name "Net-(IC3-PB13-SPI2SCK{slash}USART3CTS{slash}TIM1CH1N)") (class "Default")
      (node (ref "IC3") (pin "26") (pinfunction "PB13-SPI2SCK/USART3CTS/TIM1CH1N_26") (pintype "bidirectional"))
      (node (ref "R8") (pin "P$1") (pinfunction "1_P$1") (pintype "passive"))
    )
    (net (code "34") (name "Net-(IC3-PB14-SPI2MISO{slash}USART3RTS{slash}TIM1CH2N)") (class "Default")
      (node (ref "IC3") (pin "27") (pinfunction "PB14-SPI2MISO/USART3RTS/TIM1CH2N_27") (pintype "bidirectional"))
      (node (ref "R9") (pin "P$1") (pinfunction "1_P$1") (pintype "passive"))
    )
    (net (code "35") (name "Net-(IC3-PB15-SPI2MOSI{slash}TIM1CH3N)") (class "Default")
      (node (ref "IC3") (pin "28") (pinfunction "PB15-SPI2MOSI/TIM1CH3N_28") (pintype "bidirectional"))
      (node (ref "R10") (pin "P$1") (pinfunction "1_P$1") (pintype "passive"))
    )
    (net (code "36") (name "Net-(IC4-+IN)") (class "Default")
      (node (ref "IC4") (pin "3") (pinfunction "+IN_3") (pintype "input"))
      (node (ref "R27") (pin "P$1") (pinfunction "1_P$1") (pintype "passive"))
      (node (ref "R28") (pin "P$2") (pinfunction "2_P$2") (pintype "passive"))
      (node (ref "R29") (pin "P$2") (pinfunction "2_P$2") (pintype "passive"))
    )
    (net (code "37") (name "Net-(IC4--IN)") (class "Default")
      (node (ref "IC4") (pin "4") (pinfunction "-IN_4") (pintype "input"))
      (node (ref "R30") (pin "P$2") (pinfunction "2_P$2") (pintype "passive"))
      (node (ref "R31") (pin "P$2") (pinfunction "2_P$2") (pintype "passive"))
    )
    (net (code "38") (name "Net-(IC4-OUT)") (class "Default")
      (node (ref "IC4") (pin "1") (pinfunction "OUT_1") (pintype "output"))
      (node (ref "R31") (pin "P$1") (pinfunction "1_P$1") (pintype "passive"))
      (node (ref "R37") (pin "P$1") (pinfunction "1_P$1") (pintype "passive"))
    )
    (net (code "39") (name "Net-(IC5-RXD)") (class "Default")
      (node (ref "IC5") (pin "4") (pinfunction "RXD_4") (pintype "bidirectional"))
      (node (ref "IC6") (pin "7") (pinfunction "INA_7") (pintype "bidirectional"))
      (node (ref "R36") (pin "P$1") (pinfunction "1_P$1") (pintype "passive"))
    )
    (net (code "40") (name "Net-(IC5-TXD)") (class "Default")
      (node (ref "IC5") (pin "1") (pinfunction "TXD_1") (pintype "bidirectional"))
      (node (ref "IC6") (pin "6") (pinfunction "OUTB_6") (pintype "bidirectional"))
      (node (ref "R35") (pin "P$1") (pinfunction "1_P$1") (pintype "passive"))
    )
    (net (code "41") (name "Net-(IC7-WP)") (class "Default")
      (node (ref "IC7") (pin "5") (pinfunction "WP_5") (pintype "bidirectional"))
      (node (ref "R41") (pin "P$1") (pinfunction "1_P$1") (pintype "passive"))
    )
    (net (code "42") (name "Net-(IC11-VOUT)") (class "Default")
      (node (ref "C14") (pin "+") (pinfunction "+_+") (pintype "passive"))
      (node (ref "C15") (pin "+") (pinfunction "+_+") (pintype "passive"))
      (node (ref "D5") (pin "A") (pinfunction "A_A") (pintype "passive"))
      (node (ref "IC11") (pin "P$3") (pinfunction "VOUT_P$3") (pintype "power_in"))
    )
    (net (code "43") (name "Net-(R1-2)") (class "Default")
      (node (ref "LED1") (pin "C") (pinfunction "C_C") (pintype "passive"))
      (node (ref "R1") (pin "P$2") (pinfunction "2_P$2") (pintype "passive"))
    )
    (net (code "44") (name "Net-(R2-2)") (class "Default")
      (node (ref "LED2") (pin "C") (pinfunction "C_C") (pintype "passive"))
      (node (ref "R2") (pin "P$2") (pinfunction "2_P$2") (pintype "passive"))
    )
    (net (code "45") (name "Net-(R3-2)") (class "Default")
      (node (ref "LED3") (pin "C") (pinfunction "C_C") (pintype "passive"))
      (node (ref "R3") (pin "P$2") (pinfunction "2_P$2") (pintype "passive"))
    )
    (net (code "46") (name "Net-(R4-2)") (class "Default")
      (node (ref "LED4") (pin "C") (pinfunction "C_C") (pintype "passive"))
      (node (ref "R4") (pin "P$2") (pinfunction "2_P$2") (pintype "passive"))
    )
    (net (code "47") (name "Net-(R11-2)") (class "Default")
      (node (ref "LED5") (pin "C") (pinfunction "C_C") (pintype "passive"))
      (node (ref "R11") (pin "P$2") (pinfunction "2_P$2") (pintype "passive"))
    )
    (net (code "48") (name "Net-(R21-2)") (class "Default")
      (node (ref "R21") (pin "P$2") (pinfunction "2_P$2") (pintype "passive"))
      (node (ref "X2") (pin "2") (pinfunction "2_2") (pintype "bidirectional"))
    )
    (net (code "49") (name "Net-(R24-2)") (class "Default")
      (node (ref "R24") (pin "P$2") (pinfunction "2_P$2") (pintype "passive"))
      (node (ref "X2") (pin "3") (pinfunction "3_3") (pintype "bidirectional"))
    )
    (net (code "50") (name "PHASE_U") (class "Default")
      (node (ref "C23") (pin "-") (pinfunction "-_-") (pintype "passive"))
      (node (ref "IC2") (pin "6") (pinfunction "VS_6") (pintype "bidirectional"))
      (node (ref "R14") (pin "P$1") (pinfunction "1_P$1") (pintype "passive"))
      (node (ref "X4") (pin "3") (pinfunction "3_3") (pintype "bidirectional"))
    )
    (net (code "51") (name "PHASE_V") (class "Default")
      (node (ref "C24") (pin "-") (pinfunction "-_-") (pintype "passive"))
      (node (ref "IC9") (pin "6") (pinfunction "VS_6") (pintype "bidirectional"))
      (node (ref "R16") (pin "P$1") (pinfunction "1_P$1") (pintype "passive"))
      (node (ref "X4") (pin "9") (pinfunction "9_9") (pintype "bidirectional"))
    )
    (net (code "52") (name "PHASE_W") (class "Default")
      (node (ref "C25") (pin "-") (pinfunction "-_-") (pintype "passive"))
      (node (ref "IC10") (pin "6") (pinfunction "VS_6") (pintype "bidirectional"))
      (node (ref "R18") (pin "P$1") (pinfunction "1_P$1") (pintype "passive"))
      (node (ref "X4") (pin "8") (pinfunction "8_8") (pintype "bidirectional"))
    )
    (net (code "53") (name "RST") (class "Default")
      (node (ref "C6") (pin "P$2") (pinfunction "2_P$2") (pintype "passive"))
      (node (ref "IC3") (pin "7") (pinfunction "NRST_7") (pintype "bidirectional"))
      (node (ref "JTAG") (pin "10") (pinfunction "10_10") (pintype "bidirectional"))
    )
    (net (code "54") (name "RXD") (class "Default")
      (node (ref "IC3") (pin "43") (pinfunction "PB7-I2C1SDA/TIM4CH2-USART1RX_43") (pintype "bidirectional"))
      (node (ref "R19") (pin "P$2") (pinfunction "2_P$2") (pintype "passive"))
      (node (ref "R21") (pin "P$1") (pinfunction "1_P$1") (pintype "passive"))
    )
    (net (code "55") (name "SHUNT") (class "Default")
      (node (ref "R27") (pin "P$2") (pinfunction "2_P$2") (pintype "passive"))
      (node (ref "X4") (pin "10") (pinfunction "10_10") (pintype "bidirectional"))
    )
    (net (code "56") (name "STAR_VOLTAGE") (class "Default")
      (node (ref "R23") (pin "P$2") (pinfunction "2_P$2") (pintype "passive"))
      (node (ref "R25") (pin "P$2") (pinfunction "2_P$2") (pintype "passive"))
      (node (ref "R26") (pin "P$2") (pinfunction "2_P$2") (pintype "passive"))
      (node (ref "TP9") (pin "P$1") (pinfunction "1_P$1") (pintype "bidirectional"))
      (node (ref "U2") (pin "10") (pinfunction "-IN_10") (pintype "input"))
      (node (ref "U2") (pin "6") (pinfunction "-IN_6") (pintype "input"))
      (node (ref "U2") (pin "8") (pinfunction "-IN_8") (pintype "input"))
    )
    (net (code "57") (name "TCK") (class "Default")
      (node (ref "IC3") (pin "37") (pinfunction "PA14/JTCK/SWCLK_37") (pintype "bidirectional"))
      (node (ref "JTAG") (pin "4") (pinfunction "4_4") (pintype "bidirectional"))
    )
    (net (code "58") (name "TDI") (class "Default")
      (node (ref "IC3") (pin "38") (pinfunction "PA15/JTDI-TIM2CH1ETR/SPI1NSS_38") (pintype "bidirectional"))
      (node (ref "JTAG") (pin "8") (pinfunction "8_8") (pintype "bidirectional"))
    )
    (net (code "59") (name "TDO") (class "Default")
      (node (ref "IC3") (pin "39") (pinfunction "PB3/JTDO--TIM2CH2/TRACESWO/SPI1SCK_39") (pintype "bidirectional"))
      (node (ref "JTAG") (pin "6") (pinfunction "6_6") (pintype "bidirectional"))
    )
    (net (code "60") (name "TEMP") (class "Default")
      (node (ref "IC3") (pin "15") (pinfunction "PA5-SPI1SCK/ADC5_15") (pintype "bidirectional"))
      (node (ref "R32") (pin "P$2") (pinfunction "2_P$2") (pintype "passive"))
      (node (ref "TH1") (pin "P$1") (pinfunction "1_P$1") (pintype "passive"))
      (node (ref "TP17") (pin "P$1") (pinfunction "1_P$1") (pintype "bidirectional"))
    )
    (net (code "61") (name "TMS") (class "Default")
      (node (ref "IC3") (pin "34") (pinfunction "PA13/JTMS/SWDIO_34") (pintype "bidirectional"))
      (node (ref "JTAG") (pin "2") (pinfunction "2_2") (pintype "bidirectional"))
    )
    (net (code "62") (name "TXD") (class "Default")
      (node (ref "IC3") (pin "42") (pinfunction "PB6-I2C1SCL/TIM4CH1-USART1TX_42") (pintype "bidirectional"))
      (node (ref "R24") (pin "P$1") (pinfunction "1_P$1") (pintype "passive"))
    )
    (net (code "63") (name "USART_+5V") (class "Default")
      (node (ref "D2") (pin "A") (pinfunction "A_A") (pintype "passive"))
      (node (ref "X2") (pin "4") (pinfunction "4_4") (pintype "bidirectional"))
    )
    (net (code "64") (name "U_COMM") (class "Default")
      (node (ref "IC3") (pin "21") (pinfunction "PB10-I2C2SCL/USART3TX-TIM2CH3_21") (pintype "bidirectional"))
      (node (ref "TP6") (pin "P$1") (pinfunction "1_P$1") (pintype "bidirectional"))
      (node (ref "U2") (pin "13") (pinfunction "OUT_13") (pintype "output"))
    )
    (net (code "65") (name "U_GATE_HIGH") (class "Default")
      (node (ref "IC2") (pin "7") (pinfunction "HO_7") (pintype "bidirectional"))
      (node (ref "X4") (pin "1") (pinfunction "1_1") (pintype "bidirectional"))
    )
    (net (code "66") (name "U_GATE_LOW") (class "Default")
      (node (ref "IC2") (pin "5") (pinfunction "LO_5") (pintype "bidirectional"))
      (node (ref "X4") (pin "5") (pinfunction "5_5") (pintype "bidirectional"))
    )
    (net (code "67") (name "U_HIGH") (class "Default")
      (node (ref "IC2") (pin "2") (pinfunction "HIN_2") (pintype "bidirectional"))
      (node (ref "R5") (pin "P$1") (pinfunction "1_P$1") (pintype "passive"))
      (node (ref "TP10") (pin "P$1") (pinfunction "1_P$1") (pintype "bidirectional"))
    )
    (net (code "68") (name "U_LOW") (class "Default")
      (node (ref "IC2") (pin "3") (pinfunction "LIN_3") (pintype "bidirectional"))
      (node (ref "R8") (pin "P$2") (pinfunction "2_P$2") (pintype "passive"))
      (node (ref "TP11") (pin "P$1") (pinfunction "1_P$1") (pintype "bidirectional"))
    )
    (net (code "69") (name "U_VOLTAGE") (class "Default")
      (node (ref "C36") (pin "P$1") (pinfunction "1_P$1") (pintype "passive"))
      (node (ref "R14") (pin "P$2") (pinfunction "2_P$2") (pintype "passive"))
      (node (ref "R15") (pin "P$1") (pinfunction "1_P$1") (pintype "passive"))
      (node (ref "R23") (pin "P$1") (pinfunction "1_P$1") (pintype "passive"))
      (node (ref "R38") (pin "P$1") (pinfunction "1_P$1") (pintype "passive"))
      (node (ref "TP3") (pin "P$1") (pinfunction "1_P$1") (pintype "bidirectional"))
      (node (ref "U2") (pin "11") (pinfunction "+IN_11") (pintype "input"))
    )
    (net (code "70") (name "V_BATT") (class "Default")
      (node (ref "IC3") (pin "13") (pinfunction "PA3-USART2RX/ADC3/TIM2CH4_13") (pintype "bidirectional"))
      (node (ref "R12") (pin "P$1") (pinfunction "1_P$1") (pintype "passive"))
      (node (ref "R13") (pin "P$2") (pinfunction "2_P$2") (pintype "passive"))
    )
    (net (code "71") (name "V_COMM") (class "Default")
      (node (ref "IC3") (pin "22") (pinfunction "PB11-I2C2SDA/USART3RX-TIM2CH4_22") (pintype "bidirectional"))
      (node (ref "TP7") (pin "P$1") (pinfunction "1_P$1") (pintype "bidirectional"))
      (node (ref "U2") (pin "14") (pinfunction "OUT_14") (pintype "output"))
    )
    (net (code "72") (name "V_GATE_HIGH") (class "Default")
      (node (ref "IC9") (pin "7") (pinfunction "HO_7") (pintype "bidirectional"))
      (node (ref "X4") (pin "7") (pinfunction "7_7") (pintype "bidirectional"))
    )
    (net (code "73") (name "V_GATE_LOW") (class "Default")
      (node (ref "IC9") (pin "5") (pinfunction "LO_5") (pintype "bidirectional"))
      (node (ref "X4") (pin "11") (pinfunction "11_11") (pintype "bidirectional"))
    )
    (net (code "74") (name "V_HIGH") (class "Default")
      (node (ref "IC9") (pin "2") (pinfunction "HIN_2") (pintype "bidirectional"))
      (node (ref "R6") (pin "P$1") (pinfunction "1_P$1") (pintype "passive"))
      (node (ref "TP12") (pin "P$1") (pinfunction "1_P$1") (pintype "bidirectional"))
    )
    (net (code "75") (name "V_LOW") (class "Default")
      (node (ref "IC9") (pin "3") (pinfunction "LIN_3") (pintype "bidirectional"))
      (node (ref "R9") (pin "P$2") (pinfunction "2_P$2") (pintype "passive"))
      (node (ref "TP13") (pin "P$1") (pinfunction "1_P$1") (pintype "bidirectional"))
    )
    (net (code "76") (name "V_VOLTAGE") (class "Default")
      (node (ref "C37") (pin "P$1") (pinfunction "1_P$1") (pintype "passive"))
      (node (ref "R16") (pin "P$2") (pinfunction "2_P$2") (pintype "passive"))
      (node (ref "R17") (pin "P$1") (pinfunction "1_P$1") (pintype "passive"))
      (node (ref "R25") (pin "P$1") (pinfunction "1_P$1") (pintype "passive"))
      (node (ref "R39") (pin "P$1") (pinfunction "1_P$1") (pintype "passive"))
      (node (ref "TP4") (pin "P$1") (pinfunction "1_P$1") (pintype "bidirectional"))
      (node (ref "U2") (pin "9") (pinfunction "+IN_9") (pintype "input"))
    )
    (net (code "77") (name "W_COMM") (class "Default")
      (node (ref "IC3") (pin "25") (pinfunction "PB12-SPI2NSS/I2C2SMBAI/USART3CK/TIM1BKIN_25") (pintype "bidirectional"))
      (node (ref "TP8") (pin "P$1") (pinfunction "1_P$1") (pintype "bidirectional"))
      (node (ref "U2") (pin "1") (pinfunction "OUT_1") (pintype "output"))
    )
    (net (code "78") (name "W_GATE_HIGH") (class "Default")
      (node (ref "IC10") (pin "7") (pinfunction "HO_7") (pintype "bidirectional"))
      (node (ref "X4") (pin "13") (pinfunction "13_13") (pintype "bidirectional"))
    )
    (net (code "79") (name "W_GATE_LOW") (class "Default")
      (node (ref "IC10") (pin "5") (pinfunction "LO_5") (pintype "bidirectional"))
      (node (ref "X4") (pin "15") (pinfunction "15_15") (pintype "bidirectional"))
    )
    (net (code "80") (name "W_HIGH") (class "Default")
      (node (ref "IC10") (pin "2") (pinfunction "HIN_2") (pintype "bidirectional"))
      (node (ref "R7") (pin "P$1") (pinfunction "1_P$1") (pintype "passive"))
      (node (ref "TP14") (pin "P$1") (pinfunction "1_P$1") (pintype "bidirectional"))
    )
    (net (code "81") (name "W_LOW") (class "Default")
      (node (ref "IC10") (pin "3") (pinfunction "LIN_3") (pintype "bidirectional"))
      (node (ref "R10") (pin "P$2") (pinfunction "2_P$2") (pintype "passive"))
      (node (ref "TP15") (pin "P$1") (pinfunction "1_P$1") (pintype "bidirectional"))
    )
    (net (code "82") (name "W_VOLTAGE") (class "Default")
      (node (ref "C38") (pin "P$1") (pinfunction "1_P$1") (pintype "passive"))
      (node (ref "R18") (pin "P$2") (pinfunction "2_P$2") (pintype "passive"))
      (node (ref "R22") (pin "P$1") (pinfunction "1_P$1") (pintype "passive"))
      (node (ref "R26") (pin "P$1") (pinfunction "1_P$1") (pintype "passive"))
      (node (ref "R40") (pin "P$1") (pinfunction "1_P$1") (pintype "passive"))
      (node (ref "TP5") (pin "P$1") (pinfunction "1_P$1") (pintype "bidirectional"))
      (node (ref "U2") (pin "7") (pinfunction "+IN_7") (pintype "input"))
    )
    (net (code "83") (name "unconnected-(IC3-PB2{slash}BOOT1-Pad20)") (class "Default")
      (node (ref "IC3") (pin "20") (pinfunction "PB2/BOOT1_20") (pintype "bidirectional"))
    )
    (net (code "84") (name "unconnected-(IC3-PB4{slash}JNTRST--TIM3CH1{slash}SPI1MISO-Pad40)") (class "Default")
      (node (ref "IC3") (pin "40") (pinfunction "PB4/JNTRST--TIM3CH1/SPI1MISO_40") (pintype "bidirectional"))
    )
    (net (code "85") (name "unconnected-(IC3-PB5-I2C1SMBAI-TIM3CH2{slash}SPI1MOSI-Pad41)") (class "Default")
      (node (ref "IC3") (pin "41") (pinfunction "PB5-I2C1SMBAI-TIM3CH2/SPI1MOSI_41") (pintype "bidirectional"))
    )
    (net (code "86") (name "unconnected-(IC3-PC13-TAMPER-RTC-Pad2)") (class "Default")
      (node (ref "IC3") (pin "2") (pinfunction "PC13-TAMPER-RTC_2") (pintype "bidirectional"))
    )
    (net (code "87") (name "unconnected-(IC3-PC14-OSC32_IN-Pad3)") (class "Default")
      (node (ref "IC3") (pin "3") (pinfunction "PC14-OSC32_IN_3") (pintype "bidirectional"))
    )
    (net (code "88") (name "unconnected-(IC3-PC15-OSC32_OUT-Pad4)") (class "Default")
      (node (ref "IC3") (pin "4") (pinfunction "PC15-OSC32_OUT_4") (pintype "bidirectional"))
    )
    (net (code "89") (name "unconnected-(IC5-VREF-Pad5)") (class "Default")
      (node (ref "IC5") (pin "5") (pinfunction "VREF_5") (pintype "bidirectional"))
    )
    (net (code "90") (name "unconnected-(U2A-OUT-Pad2)") (class "Default")
      (node (ref "U2") (pin "2") (pinfunction "OUT_2") (pintype "output"))
    )
  )
)
